# CONN.net
KiCad netlist of a schematic drawn in Altium Designer
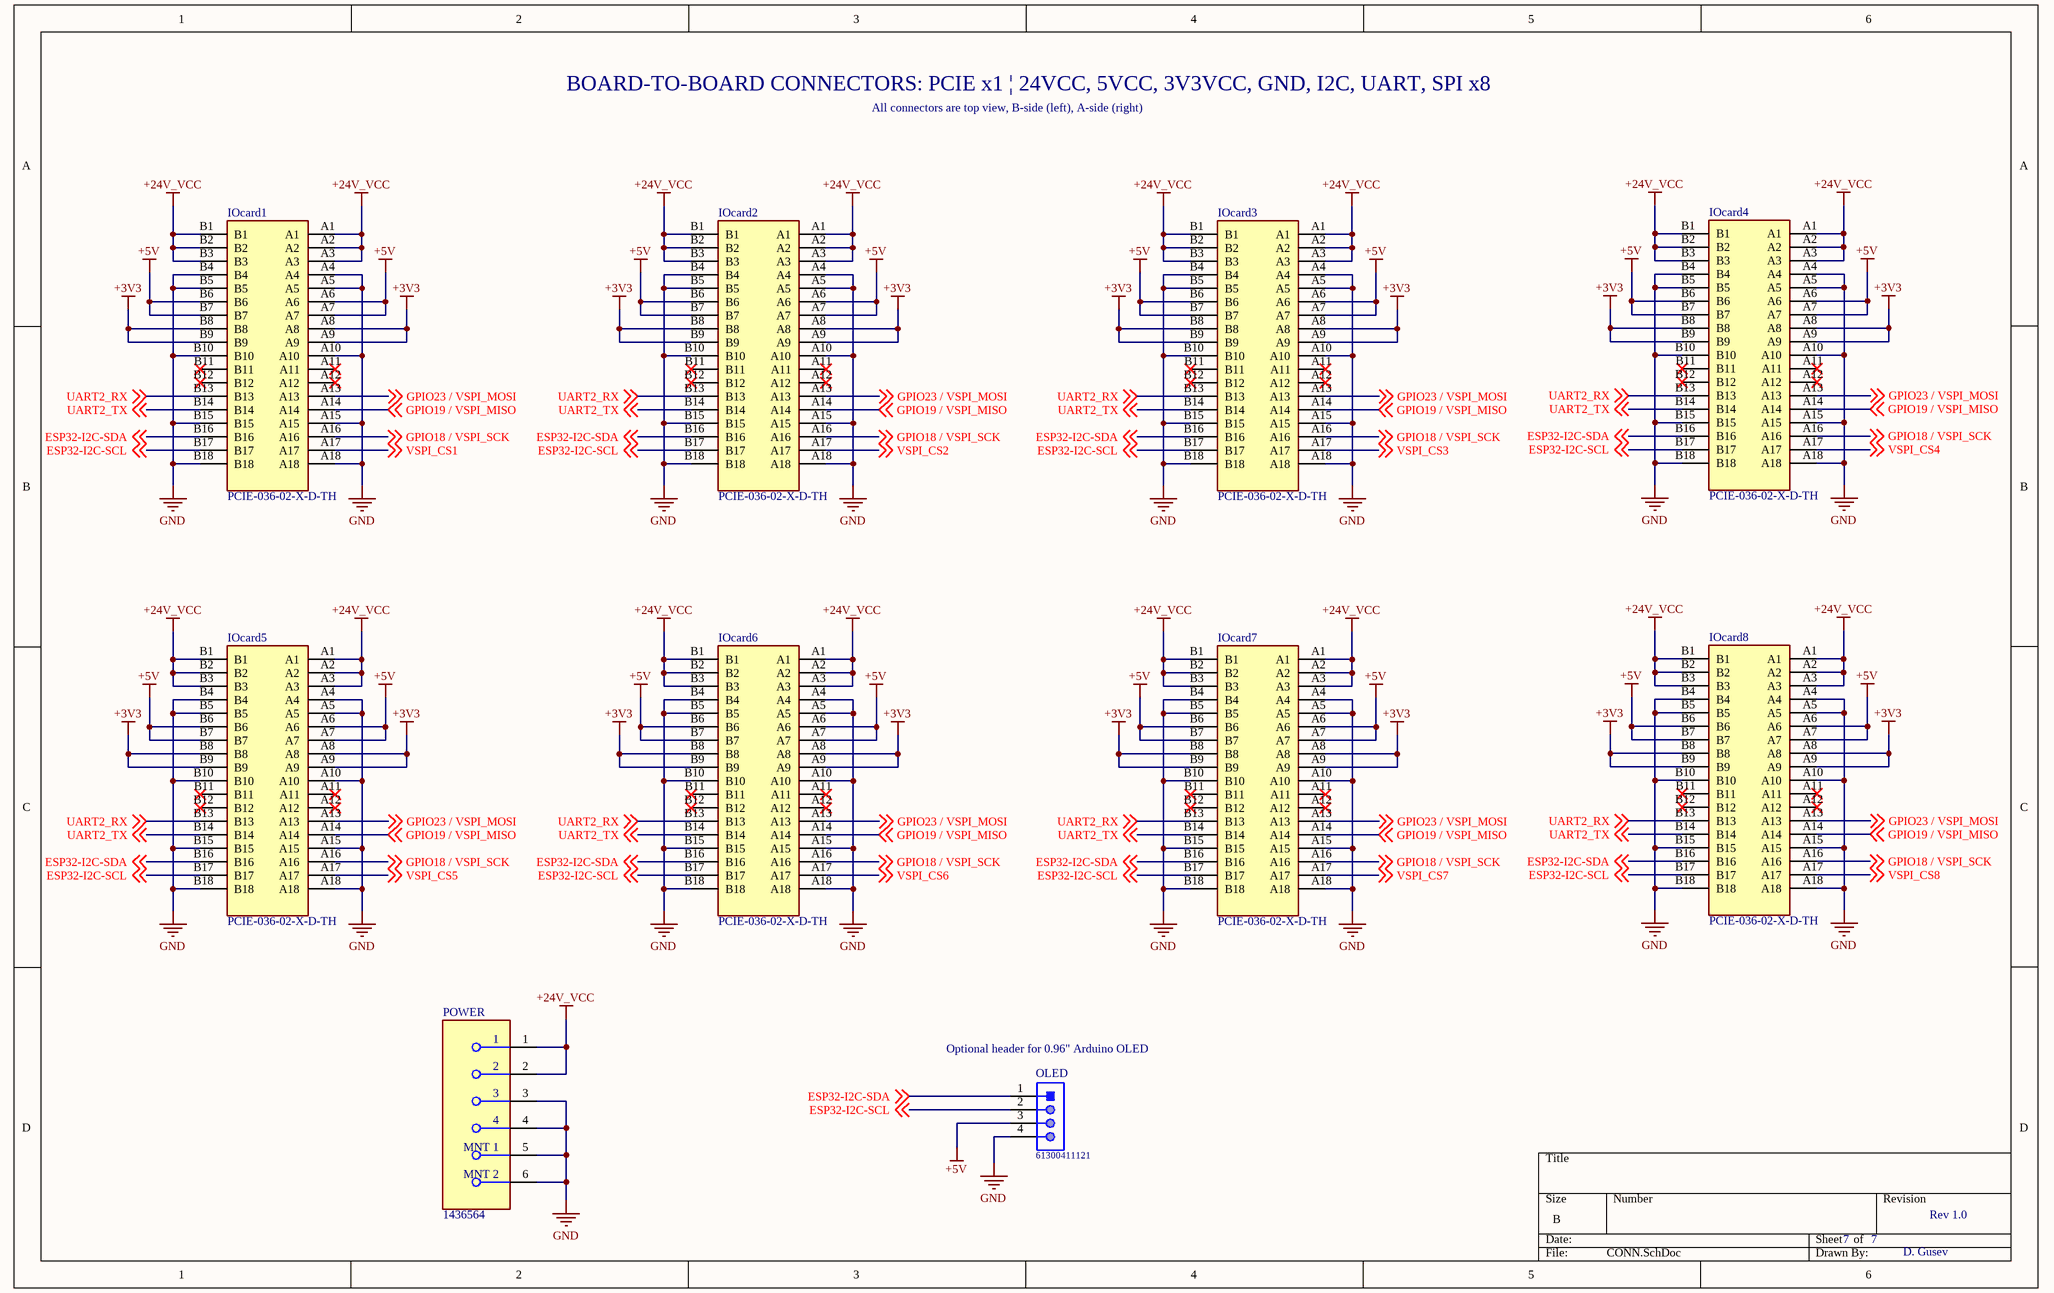
[diagram p0: CONN.SchDoc]

(export (version "E")
  (design (tool "Eeschema 10.0.6"))
  (components
    (comp (ref "IOcard1")
      (value "PCIE-036-02-X-D-TH")
      (footprint "SAMTEC_PCIE-036-02-X-D-TH")
      (description "1.00 mm PCI ExpressÂ® Edge Card Connector")
      (fields (field (name "MF") "Samtec"))
      (libsource (lib "ESP32_INDUSTRIAL_IO_BASEBOARD") (part "PCIE-036-02-X-D-TH"))
    )
    (comp (ref "IOcard2")
      (value "PCIE-036-02-X-D-TH")
      (footprint "SAMTEC_PCIE-036-02-X-D-TH")
      (description "1.00 mm PCI ExpressÂ® Edge Card Connector")
      (fields (field (name "MF") "Samtec"))
      (libsource (lib "ESP32_INDUSTRIAL_IO_BASEBOARD") (part "PCIE-036-02-X-D-TH"))
    )
    (comp (ref "IOcard3")
      (value "PCIE-036-02-X-D-TH")
      (footprint "SAMTEC_PCIE-036-02-X-D-TH")
      (description "1.00 mm PCI ExpressÂ® Edge Card Connector")
      (fields (field (name "MF") "Samtec"))
      (libsource (lib "ESP32_INDUSTRIAL_IO_BASEBOARD") (part "PCIE-036-02-X-D-TH"))
    )
    (comp (ref "IOcard4")
      (value "PCIE-036-02-X-D-TH")
      (footprint "SAMTEC_PCIE-036-02-X-D-TH")
      (description "1.00 mm PCI ExpressÂ® Edge Card Connector")
      (fields (field (name "MF") "Samtec"))
      (libsource (lib "ESP32_INDUSTRIAL_IO_BASEBOARD") (part "PCIE-036-02-X-D-TH"))
    )
    (comp (ref "IOcard5")
      (value "PCIE-036-02-X-D-TH")
      (footprint "SAMTEC_PCIE-036-02-X-D-TH")
      (description "1.00 mm PCI ExpressÂ® Edge Card Connector")
      (fields (field (name "MF") "Samtec"))
      (libsource (lib "ESP32_INDUSTRIAL_IO_BASEBOARD") (part "PCIE-036-02-X-D-TH"))
    )
    (comp (ref "IOcard6")
      (value "PCIE-036-02-X-D-TH")
      (footprint "SAMTEC_PCIE-036-02-X-D-TH")
      (description "1.00 mm PCI ExpressÂ® Edge Card Connector")
      (fields (field (name "MF") "Samtec"))
      (libsource (lib "ESP32_INDUSTRIAL_IO_BASEBOARD") (part "PCIE-036-02-X-D-TH"))
    )
    (comp (ref "IOcard7")
      (value "PCIE-036-02-X-D-TH")
      (footprint "SAMTEC_PCIE-036-02-X-D-TH")
      (description "1.00 mm PCI ExpressÂ® Edge Card Connector")
      (fields (field (name "MF") "Samtec"))
      (libsource (lib "ESP32_INDUSTRIAL_IO_BASEBOARD") (part "PCIE-036-02-X-D-TH"))
    )
    (comp (ref "IOcard8")
      (value "PCIE-036-02-X-D-TH")
      (footprint "SAMTEC_PCIE-036-02-X-D-TH")
      (description "1.00 mm PCI ExpressÂ® Edge Card Connector")
      (fields (field (name "MF") "Samtec"))
      (libsource (lib "ESP32_INDUSTRIAL_IO_BASEBOARD") (part "PCIE-036-02-X-D-TH"))
    )
    (comp (ref "OLED")
      (value "61300411121")
      (footprint "61300411121")
      (description "THT Vertical Pin Header WR-PHD, Pitch 2.54 mm, Single Row, 4 pins")
      (fields (field (name "MANUFACTURER") "Wurth Elektronik") (field (name "PUBLISHER") "WurthElektronik"))
      (libsource (lib "Altium Content Vault") (part "WE-CN-1P-M-R4"))
    )
    (comp (ref "POWER")
      (value "1436564")
      (footprint "FP-1436564-MFG")
      (description "Circular Metric Connectors FEMALE 4P A-CODED")
      (fields (field (name "OCTOPART") "https://octopart.com/1436564-phoenix+contact-12805506"))
      (libsource (lib "Altium Content Vault") (part "3cf8230c7ca2247c71501eddf00a6f6"))
    )
  )
  (nets
    (net (code "1") (name "+3V3") (class "Default")
      (node (ref "IOcard1") (pin "A8") (pinfunction "A8_A8") (pintype "passive"))
      (node (ref "IOcard1") (pin "A9") (pinfunction "A9_A9") (pintype "passive"))
      (node (ref "IOcard1") (pin "B8") (pinfunction "B8_B8") (pintype "passive"))
      (node (ref "IOcard1") (pin "B9") (pinfunction "B9_B9") (pintype "passive"))
      (node (ref "IOcard2") (pin "A8") (pinfunction "A8_A8") (pintype "passive"))
      (node (ref "IOcard2") (pin "A9") (pinfunction "A9_A9") (pintype "passive"))
      (node (ref "IOcard2") (pin "B8") (pinfunction "B8_B8") (pintype "passive"))
      (node (ref "IOcard2") (pin "B9") (pinfunction "B9_B9") (pintype "passive"))
      (node (ref "IOcard3") (pin "A8") (pinfunction "A8_A8") (pintype "passive"))
      (node (ref "IOcard3") (pin "A9") (pinfunction "A9_A9") (pintype "passive"))
      (node (ref "IOcard3") (pin "B8") (pinfunction "B8_B8") (pintype "passive"))
      (node (ref "IOcard3") (pin "B9") (pinfunction "B9_B9") (pintype "passive"))
      (node (ref "IOcard4") (pin "A8") (pinfunction "A8_A8") (pintype "passive"))
      (node (ref "IOcard4") (pin "A9") (pinfunction "A9_A9") (pintype "passive"))
      (node (ref "IOcard4") (pin "B8") (pinfunction "B8_B8") (pintype "passive"))
      (node (ref "IOcard4") (pin "B9") (pinfunction "B9_B9") (pintype "passive"))
      (node (ref "IOcard5") (pin "A8") (pinfunction "A8_A8") (pintype "passive"))
      (node (ref "IOcard5") (pin "A9") (pinfunction "A9_A9") (pintype "passive"))
      (node (ref "IOcard5") (pin "B8") (pinfunction "B8_B8") (pintype "passive"))
      (node (ref "IOcard5") (pin "B9") (pinfunction "B9_B9") (pintype "passive"))
      (node (ref "IOcard6") (pin "A8") (pinfunction "A8_A8") (pintype "passive"))
      (node (ref "IOcard6") (pin "A9") (pinfunction "A9_A9") (pintype "passive"))
      (node (ref "IOcard6") (pin "B8") (pinfunction "B8_B8") (pintype "passive"))
      (node (ref "IOcard6") (pin "B9") (pinfunction "B9_B9") (pintype "passive"))
      (node (ref "IOcard7") (pin "A8") (pinfunction "A8_A8") (pintype "passive"))
      (node (ref "IOcard7") (pin "A9") (pinfunction "A9_A9") (pintype "passive"))
      (node (ref "IOcard7") (pin "B8") (pinfunction "B8_B8") (pintype "passive"))
      (node (ref "IOcard7") (pin "B9") (pinfunction "B9_B9") (pintype "passive"))
      (node (ref "IOcard8") (pin "A8") (pinfunction "A8_A8") (pintype "passive"))
      (node (ref "IOcard8") (pin "A9") (pinfunction "A9_A9") (pintype "passive"))
      (node (ref "IOcard8") (pin "B8") (pinfunction "B8_B8") (pintype "passive"))
      (node (ref "IOcard8") (pin "B9") (pinfunction "B9_B9") (pintype "passive"))
    )
    (net (code "2") (name "+5V") (class "Default")
      (node (ref "IOcard1") (pin "A6") (pinfunction "A6_A6") (pintype "passive"))
      (node (ref "IOcard1") (pin "A7") (pinfunction "A7_A7") (pintype "passive"))
      (node (ref "IOcard1") (pin "B6") (pinfunction "B6_B6") (pintype "passive"))
      (node (ref "IOcard1") (pin "B7") (pinfunction "B7_B7") (pintype "passive"))
      (node (ref "IOcard2") (pin "A6") (pinfunction "A6_A6") (pintype "passive"))
      (node (ref "IOcard2") (pin "A7") (pinfunction "A7_A7") (pintype "passive"))
      (node (ref "IOcard2") (pin "B6") (pinfunction "B6_B6") (pintype "passive"))
      (node (ref "IOcard2") (pin "B7") (pinfunction "B7_B7") (pintype "passive"))
      (node (ref "IOcard3") (pin "A6") (pinfunction "A6_A6") (pintype "passive"))
      (node (ref "IOcard3") (pin "A7") (pinfunction "A7_A7") (pintype "passive"))
      (node (ref "IOcard3") (pin "B6") (pinfunction "B6_B6") (pintype "passive"))
      (node (ref "IOcard3") (pin "B7") (pinfunction "B7_B7") (pintype "passive"))
      (node (ref "IOcard4") (pin "A6") (pinfunction "A6_A6") (pintype "passive"))
      (node (ref "IOcard4") (pin "A7") (pinfunction "A7_A7") (pintype "passive"))
      (node (ref "IOcard4") (pin "B6") (pinfunction "B6_B6") (pintype "passive"))
      (node (ref "IOcard4") (pin "B7") (pinfunction "B7_B7") (pintype "passive"))
      (node (ref "IOcard5") (pin "A6") (pinfunction "A6_A6") (pintype "passive"))
      (node (ref "IOcard5") (pin "A7") (pinfunction "A7_A7") (pintype "passive"))
      (node (ref "IOcard5") (pin "B6") (pinfunction "B6_B6") (pintype "passive"))
      (node (ref "IOcard5") (pin "B7") (pinfunction "B7_B7") (pintype "passive"))
      (node (ref "IOcard6") (pin "A6") (pinfunction "A6_A6") (pintype "passive"))
      (node (ref "IOcard6") (pin "A7") (pinfunction "A7_A7") (pintype "passive"))
      (node (ref "IOcard6") (pin "B6") (pinfunction "B6_B6") (pintype "passive"))
      (node (ref "IOcard6") (pin "B7") (pinfunction "B7_B7") (pintype "passive"))
      (node (ref "IOcard7") (pin "A6") (pinfunction "A6_A6") (pintype "passive"))
      (node (ref "IOcard7") (pin "A7") (pinfunction "A7_A7") (pintype "passive"))
      (node (ref "IOcard7") (pin "B6") (pinfunction "B6_B6") (pintype "passive"))
      (node (ref "IOcard7") (pin "B7") (pinfunction "B7_B7") (pintype "passive"))
      (node (ref "IOcard8") (pin "A6") (pinfunction "A6_A6") (pintype "passive"))
      (node (ref "IOcard8") (pin "A7") (pinfunction "A7_A7") (pintype "passive"))
      (node (ref "IOcard8") (pin "B6") (pinfunction "B6_B6") (pintype "passive"))
      (node (ref "IOcard8") (pin "B7") (pinfunction "B7_B7") (pintype "passive"))
      (node (ref "OLED") (pin "3") (pinfunction "3_3") (pintype "passive"))
    )
    (net (code "3") (name "+24V_VCC") (class "Default")
      (node (ref "IOcard1") (pin "A1") (pinfunction "A1_A1") (pintype "passive"))
      (node (ref "IOcard1") (pin "A2") (pinfunction "A2_A2") (pintype "passive"))
      (node (ref "IOcard1") (pin "A3") (pinfunction "A3_A3") (pintype "passive"))
      (node (ref "IOcard1") (pin "B1") (pinfunction "B1_B1") (pintype "passive"))
      (node (ref "IOcard1") (pin "B2") (pinfunction "B2_B2") (pintype "passive"))
      (node (ref "IOcard1") (pin "B3") (pinfunction "B3_B3") (pintype "passive"))
      (node (ref "IOcard2") (pin "A1") (pinfunction "A1_A1") (pintype "passive"))
      (node (ref "IOcard2") (pin "A2") (pinfunction "A2_A2") (pintype "passive"))
      (node (ref "IOcard2") (pin "A3") (pinfunction "A3_A3") (pintype "passive"))
      (node (ref "IOcard2") (pin "B1") (pinfunction "B1_B1") (pintype "passive"))
      (node (ref "IOcard2") (pin "B2") (pinfunction "B2_B2") (pintype "passive"))
      (node (ref "IOcard2") (pin "B3") (pinfunction "B3_B3") (pintype "passive"))
      (node (ref "IOcard3") (pin "A1") (pinfunction "A1_A1") (pintype "passive"))
      (node (ref "IOcard3") (pin "A2") (pinfunction "A2_A2") (pintype "passive"))
      (node (ref "IOcard3") (pin "A3") (pinfunction "A3_A3") (pintype "passive"))
      (node (ref "IOcard3") (pin "B1") (pinfunction "B1_B1") (pintype "passive"))
      (node (ref "IOcard3") (pin "B2") (pinfunction "B2_B2") (pintype "passive"))
      (node (ref "IOcard3") (pin "B3") (pinfunction "B3_B3") (pintype "passive"))
      (node (ref "IOcard4") (pin "A1") (pinfunction "A1_A1") (pintype "passive"))
      (node (ref "IOcard4") (pin "A2") (pinfunction "A2_A2") (pintype "passive"))
      (node (ref "IOcard4") (pin "A3") (pinfunction "A3_A3") (pintype "passive"))
      (node (ref "IOcard4") (pin "B1") (pinfunction "B1_B1") (pintype "passive"))
      (node (ref "IOcard4") (pin "B2") (pinfunction "B2_B2") (pintype "passive"))
      (node (ref "IOcard4") (pin "B3") (pinfunction "B3_B3") (pintype "passive"))
      (node (ref "IOcard5") (pin "A1") (pinfunction "A1_A1") (pintype "passive"))
      (node (ref "IOcard5") (pin "A2") (pinfunction "A2_A2") (pintype "passive"))
      (node (ref "IOcard5") (pin "A3") (pinfunction "A3_A3") (pintype "passive"))
      (node (ref "IOcard5") (pin "B1") (pinfunction "B1_B1") (pintype "passive"))
      (node (ref "IOcard5") (pin "B2") (pinfunction "B2_B2") (pintype "passive"))
      (node (ref "IOcard5") (pin "B3") (pinfunction "B3_B3") (pintype "passive"))
      (node (ref "IOcard6") (pin "A1") (pinfunction "A1_A1") (pintype "passive"))
      (node (ref "IOcard6") (pin "A2") (pinfunction "A2_A2") (pintype "passive"))
      (node (ref "IOcard6") (pin "A3") (pinfunction "A3_A3") (pintype "passive"))
      (node (ref "IOcard6") (pin "B1") (pinfunction "B1_B1") (pintype "passive"))
      (node (ref "IOcard6") (pin "B2") (pinfunction "B2_B2") (pintype "passive"))
      (node (ref "IOcard6") (pin "B3") (pinfunction "B3_B3") (pintype "passive"))
      (node (ref "IOcard7") (pin "A1") (pinfunction "A1_A1") (pintype "passive"))
      (node (ref "IOcard7") (pin "A2") (pinfunction "A2_A2") (pintype "passive"))
      (node (ref "IOcard7") (pin "A3") (pinfunction "A3_A3") (pintype "passive"))
      (node (ref "IOcard7") (pin "B1") (pinfunction "B1_B1") (pintype "passive"))
      (node (ref "IOcard7") (pin "B2") (pinfunction "B2_B2") (pintype "passive"))
      (node (ref "IOcard7") (pin "B3") (pinfunction "B3_B3") (pintype "passive"))
      (node (ref "IOcard8") (pin "A1") (pinfunction "A1_A1") (pintype "passive"))
      (node (ref "IOcard8") (pin "A2") (pinfunction "A2_A2") (pintype "passive"))
      (node (ref "IOcard8") (pin "A3") (pinfunction "A3_A3") (pintype "passive"))
      (node (ref "IOcard8") (pin "B1") (pinfunction "B1_B1") (pintype "passive"))
      (node (ref "IOcard8") (pin "B2") (pinfunction "B2_B2") (pintype "passive"))
      (node (ref "IOcard8") (pin "B3") (pinfunction "B3_B3") (pintype "passive"))
      (node (ref "POWER") (pin "1") (pinfunction "1_1") (pintype "passive"))
      (node (ref "POWER") (pin "2") (pinfunction "2_2") (pintype "passive"))
    )
    (net (code "4") (name "ESP32-I2C-SCL") (class "Default")
      (node (ref "IOcard1") (pin "B17") (pinfunction "B17_B17") (pintype "passive"))
      (node (ref "IOcard2") (pin "B17") (pinfunction "B17_B17") (pintype "passive"))
      (node (ref "IOcard3") (pin "B17") (pinfunction "B17_B17") (pintype "passive"))
      (node (ref "IOcard4") (pin "B17") (pinfunction "B17_B17") (pintype "passive"))
      (node (ref "IOcard5") (pin "B17") (pinfunction "B17_B17") (pintype "passive"))
      (node (ref "IOcard6") (pin "B17") (pinfunction "B17_B17") (pintype "passive"))
      (node (ref "IOcard7") (pin "B17") (pinfunction "B17_B17") (pintype "passive"))
      (node (ref "IOcard8") (pin "B17") (pinfunction "B17_B17") (pintype "passive"))
      (node (ref "OLED") (pin "2") (pinfunction "2_2") (pintype "passive"))
    )
    (net (code "5") (name "ESP32-I2C-SDA") (class "Default")
      (node (ref "IOcard1") (pin "B16") (pinfunction "B16_B16") (pintype "passive"))
      (node (ref "IOcard2") (pin "B16") (pinfunction "B16_B16") (pintype "passive"))
      (node (ref "IOcard3") (pin "B16") (pinfunction "B16_B16") (pintype "passive"))
      (node (ref "IOcard4") (pin "B16") (pinfunction "B16_B16") (pintype "passive"))
      (node (ref "IOcard5") (pin "B16") (pinfunction "B16_B16") (pintype "passive"))
      (node (ref "IOcard6") (pin "B16") (pinfunction "B16_B16") (pintype "passive"))
      (node (ref "IOcard7") (pin "B16") (pinfunction "B16_B16") (pintype "passive"))
      (node (ref "IOcard8") (pin "B16") (pinfunction "B16_B16") (pintype "passive"))
      (node (ref "OLED") (pin "1") (pinfunction "1_1") (pintype "passive"))
    )
    (net (code "6") (name "GND") (class "Default")
      (node (ref "IOcard1") (pin "A10") (pinfunction "A10_A10") (pintype "passive"))
      (node (ref "IOcard1") (pin "A15") (pinfunction "A15_A15") (pintype "passive"))
      (node (ref "IOcard1") (pin "A18") (pinfunction "A18_A18") (pintype "passive"))
      (node (ref "IOcard1") (pin "A4") (pinfunction "A4_A4") (pintype "passive"))
      (node (ref "IOcard1") (pin "A5") (pinfunction "A5_A5") (pintype "passive"))
      (node (ref "IOcard1") (pin "B10") (pinfunction "B10_B10") (pintype "passive"))
      (node (ref "IOcard1") (pin "B15") (pinfunction "B15_B15") (pintype "passive"))
      (node (ref "IOcard1") (pin "B18") (pinfunction "B18_B18") (pintype "passive"))
      (node (ref "IOcard1") (pin "B4") (pinfunction "B4_B4") (pintype "passive"))
      (node (ref "IOcard1") (pin "B5") (pinfunction "B5_B5") (pintype "passive"))
      (node (ref "IOcard2") (pin "A10") (pinfunction "A10_A10") (pintype "passive"))
      (node (ref "IOcard2") (pin "A15") (pinfunction "A15_A15") (pintype "passive"))
      (node (ref "IOcard2") (pin "A18") (pinfunction "A18_A18") (pintype "passive"))
      (node (ref "IOcard2") (pin "A4") (pinfunction "A4_A4") (pintype "passive"))
      (node (ref "IOcard2") (pin "A5") (pinfunction "A5_A5") (pintype "passive"))
      (node (ref "IOcard2") (pin "B10") (pinfunction "B10_B10") (pintype "passive"))
      (node (ref "IOcard2") (pin "B15") (pinfunction "B15_B15") (pintype "passive"))
      (node (ref "IOcard2") (pin "B18") (pinfunction "B18_B18") (pintype "passive"))
      (node (ref "IOcard2") (pin "B4") (pinfunction "B4_B4") (pintype "passive"))
      (node (ref "IOcard2") (pin "B5") (pinfunction "B5_B5") (pintype "passive"))
      (node (ref "IOcard3") (pin "A10") (pinfunction "A10_A10") (pintype "passive"))
      (node (ref "IOcard3") (pin "A15") (pinfunction "A15_A15") (pintype "passive"))
      (node (ref "IOcard3") (pin "A18") (pinfunction "A18_A18") (pintype "passive"))
      (node (ref "IOcard3") (pin "A4") (pinfunction "A4_A4") (pintype "passive"))
      (node (ref "IOcard3") (pin "A5") (pinfunction "A5_A5") (pintype "passive"))
      (node (ref "IOcard3") (pin "B10") (pinfunction "B10_B10") (pintype "passive"))
      (node (ref "IOcard3") (pin "B15") (pinfunction "B15_B15") (pintype "passive"))
      (node (ref "IOcard3") (pin "B18") (pinfunction "B18_B18") (pintype "passive"))
      (node (ref "IOcard3") (pin "B4") (pinfunction "B4_B4") (pintype "passive"))
      (node (ref "IOcard3") (pin "B5") (pinfunction "B5_B5") (pintype "passive"))
      (node (ref "IOcard4") (pin "A10") (pinfunction "A10_A10") (pintype "passive"))
      (node (ref "IOcard4") (pin "A15") (pinfunction "A15_A15") (pintype "passive"))
      (node (ref "IOcard4") (pin "A18") (pinfunction "A18_A18") (pintype "passive"))
      (node (ref "IOcard4") (pin "A4") (pinfunction "A4_A4") (pintype "passive"))
      (node (ref "IOcard4") (pin "A5") (pinfunction "A5_A5") (pintype "passive"))
      (node (ref "IOcard4") (pin "B10") (pinfunction "B10_B10") (pintype "passive"))
      (node (ref "IOcard4") (pin "B15") (pinfunction "B15_B15") (pintype "passive"))
      (node (ref "IOcard4") (pin "B18") (pinfunction "B18_B18") (pintype "passive"))
      (node (ref "IOcard4") (pin "B4") (pinfunction "B4_B4") (pintype "passive"))
      (node (ref "IOcard4") (pin "B5") (pinfunction "B5_B5") (pintype "passive"))
      (node (ref "IOcard5") (pin "A10") (pinfunction "A10_A10") (pintype "passive"))
      (node (ref "IOcard5") (pin "A15") (pinfunction "A15_A15") (pintype "passive"))
      (node (ref "IOcard5") (pin "A18") (pinfunction "A18_A18") (pintype "passive"))
      (node (ref "IOcard5") (pin "A4") (pinfunction "A4_A4") (pintype "passive"))
      (node (ref "IOcard5") (pin "A5") (pinfunction "A5_A5") (pintype "passive"))
      (node (ref "IOcard5") (pin "B10") (pinfunction "B10_B10") (pintype "passive"))
      (node (ref "IOcard5") (pin "B15") (pinfunction "B15_B15") (pintype "passive"))
      (node (ref "IOcard5") (pin "B18") (pinfunction "B18_B18") (pintype "passive"))
      (node (ref "IOcard5") (pin "B4") (pinfunction "B4_B4") (pintype "passive"))
      (node (ref "IOcard5") (pin "B5") (pinfunction "B5_B5") (pintype "passive"))
      (node (ref "IOcard6") (pin "A10") (pinfunction "A10_A10") (pintype "passive"))
      (node (ref "IOcard6") (pin "A15") (pinfunction "A15_A15") (pintype "passive"))
      (node (ref "IOcard6") (pin "A18") (pinfunction "A18_A18") (pintype "passive"))
      (node (ref "IOcard6") (pin "A4") (pinfunction "A4_A4") (pintype "passive"))
      (node (ref "IOcard6") (pin "A5") (pinfunction "A5_A5") (pintype "passive"))
      (node (ref "IOcard6") (pin "B10") (pinfunction "B10_B10") (pintype "passive"))
      (node (ref "IOcard6") (pin "B15") (pinfunction "B15_B15") (pintype "passive"))
      (node (ref "IOcard6") (pin "B18") (pinfunction "B18_B18") (pintype "passive"))
      (node (ref "IOcard6") (pin "B4") (pinfunction "B4_B4") (pintype "passive"))
      (node (ref "IOcard6") (pin "B5") (pinfunction "B5_B5") (pintype "passive"))
      (node (ref "IOcard7") (pin "A10") (pinfunction "A10_A10") (pintype "passive"))
      (node (ref "IOcard7") (pin "A15") (pinfunction "A15_A15") (pintype "passive"))
      (node (ref "IOcard7") (pin "A18") (pinfunction "A18_A18") (pintype "passive"))
      (node (ref "IOcard7") (pin "A4") (pinfunction "A4_A4") (pintype "passive"))
      (node (ref "IOcard7") (pin "A5") (pinfunction "A5_A5") (pintype "passive"))
      (node (ref "IOcard7") (pin "B10") (pinfunction "B10_B10") (pintype "passive"))
      (node (ref "IOcard7") (pin "B15") (pinfunction "B15_B15") (pintype "passive"))
      (node (ref "IOcard7") (pin "B18") (pinfunction "B18_B18") (pintype "passive"))
      (node (ref "IOcard7") (pin "B4") (pinfunction "B4_B4") (pintype "passive"))
      (node (ref "IOcard7") (pin "B5") (pinfunction "B5_B5") (pintype "passive"))
      (node (ref "IOcard8") (pin "A10") (pinfunction "A10_A10") (pintype "passive"))
      (node (ref "IOcard8") (pin "A15") (pinfunction "A15_A15") (pintype "passive"))
      (node (ref "IOcard8") (pin "A18") (pinfunction "A18_A18") (pintype "passive"))
      (node (ref "IOcard8") (pin "A4") (pinfunction "A4_A4") (pintype "passive"))
      (node (ref "IOcard8") (pin "A5") (pinfunction "A5_A5") (pintype "passive"))
      (node (ref "IOcard8") (pin "B10") (pinfunction "B10_B10") (pintype "passive"))
      (node (ref "IOcard8") (pin "B15") (pinfunction "B15_B15") (pintype "passive"))
      (node (ref "IOcard8") (pin "B18") (pinfunction "B18_B18") (pintype "passive"))
      (node (ref "IOcard8") (pin "B4") (pinfunction "B4_B4") (pintype "passive"))
      (node (ref "IOcard8") (pin "B5") (pinfunction "B5_B5") (pintype "passive"))
      (node (ref "OLED") (pin "4") (pinfunction "4_4") (pintype "passive"))
      (node (ref "POWER") (pin "3") (pinfunction "3_3") (pintype "passive"))
      (node (ref "POWER") (pin "4") (pinfunction "4_4") (pintype "passive"))
      (node (ref "POWER") (pin "5") (pinfunction "MNT_1_5") (pintype "passive"))
      (node (ref "POWER") (pin "6") (pinfunction "MNT_2_6") (pintype "passive"))
    )
    (net (code "7") (name "GPIO18 {slash} VSPI_SCK") (class "Default")
      (node (ref "IOcard1") (pin "A16") (pinfunction "A16_A16") (pintype "passive"))
      (node (ref "IOcard2") (pin "A16") (pinfunction "A16_A16") (pintype "passive"))
      (node (ref "IOcard3") (pin "A16") (pinfunction "A16_A16") (pintype "passive"))
      (node (ref "IOcard4") (pin "A16") (pinfunction "A16_A16") (pintype "passive"))
      (node (ref "IOcard5") (pin "A16") (pinfunction "A16_A16") (pintype "passive"))
      (node (ref "IOcard6") (pin "A16") (pinfunction "A16_A16") (pintype "passive"))
      (node (ref "IOcard7") (pin "A16") (pinfunction "A16_A16") (pintype "passive"))
      (node (ref "IOcard8") (pin "A16") (pinfunction "A16_A16") (pintype "passive"))
    )
    (net (code "8") (name "GPIO19 {slash} VSPI_MISO") (class "Default")
      (node (ref "IOcard1") (pin "A14") (pinfunction "A14_A14") (pintype "passive"))
      (node (ref "IOcard2") (pin "A14") (pinfunction "A14_A14") (pintype "passive"))
      (node (ref "IOcard3") (pin "A14") (pinfunction "A14_A14") (pintype "passive"))
      (node (ref "IOcard4") (pin "A14") (pinfunction "A14_A14") (pintype "passive"))
      (node (ref "IOcard5") (pin "A14") (pinfunction "A14_A14") (pintype "passive"))
      (node (ref "IOcard6") (pin "A14") (pinfunction "A14_A14") (pintype "passive"))
      (node (ref "IOcard7") (pin "A14") (pinfunction "A14_A14") (pintype "passive"))
      (node (ref "IOcard8") (pin "A14") (pinfunction "A14_A14") (pintype "passive"))
    )
    (net (code "9") (name "GPIO23 {slash} VSPI_MOSI") (class "Default")
      (node (ref "IOcard1") (pin "A13") (pinfunction "A13_A13") (pintype "passive"))
      (node (ref "IOcard2") (pin "A13") (pinfunction "A13_A13") (pintype "passive"))
      (node (ref "IOcard3") (pin "A13") (pinfunction "A13_A13") (pintype "passive"))
      (node (ref "IOcard4") (pin "A13") (pinfunction "A13_A13") (pintype "passive"))
      (node (ref "IOcard5") (pin "A13") (pinfunction "A13_A13") (pintype "passive"))
      (node (ref "IOcard6") (pin "A13") (pinfunction "A13_A13") (pintype "passive"))
      (node (ref "IOcard7") (pin "A13") (pinfunction "A13_A13") (pintype "passive"))
      (node (ref "IOcard8") (pin "A13") (pinfunction "A13_A13") (pintype "passive"))
    )
    (net (code "10") (name "UART2_RX") (class "Default")
      (node (ref "IOcard1") (pin "B13") (pinfunction "B13_B13") (pintype "passive"))
      (node (ref "IOcard2") (pin "B13") (pinfunction "B13_B13") (pintype "passive"))
      (node (ref "IOcard3") (pin "B13") (pinfunction "B13_B13") (pintype "passive"))
      (node (ref "IOcard4") (pin "B13") (pinfunction "B13_B13") (pintype "passive"))
      (node (ref "IOcard5") (pin "B13") (pinfunction "B13_B13") (pintype "passive"))
      (node (ref "IOcard6") (pin "B13") (pinfunction "B13_B13") (pintype "passive"))
      (node (ref "IOcard7") (pin "B13") (pinfunction "B13_B13") (pintype "passive"))
      (node (ref "IOcard8") (pin "B13") (pinfunction "B13_B13") (pintype "passive"))
    )
    (net (code "11") (name "UART2_TX") (class "Default")
      (node (ref "IOcard1") (pin "B14") (pinfunction "B14_B14") (pintype "passive"))
      (node (ref "IOcard2") (pin "B14") (pinfunction "B14_B14") (pintype "passive"))
      (node (ref "IOcard3") (pin "B14") (pinfunction "B14_B14") (pintype "passive"))
      (node (ref "IOcard4") (pin "B14") (pinfunction "B14_B14") (pintype "passive"))
      (node (ref "IOcard5") (pin "B14") (pinfunction "B14_B14") (pintype "passive"))
      (node (ref "IOcard6") (pin "B14") (pinfunction "B14_B14") (pintype "passive"))
      (node (ref "IOcard7") (pin "B14") (pinfunction "B14_B14") (pintype "passive"))
      (node (ref "IOcard8") (pin "B14") (pinfunction "B14_B14") (pintype "passive"))
    )
    (net (code "12") (name "VSPI_CS1") (class "Default")
      (node (ref "IOcard1") (pin "A17") (pinfunction "A17_A17") (pintype "passive"))
    )
    (net (code "13") (name "VSPI_CS2") (class "Default")
      (node (ref "IOcard2") (pin "A17") (pinfunction "A17_A17") (pintype "passive"))
    )
    (net (code "14") (name "VSPI_CS3") (class "Default")
      (node (ref "IOcard3") (pin "A17") (pinfunction "A17_A17") (pintype "passive"))
    )
    (net (code "15") (name "VSPI_CS4") (class "Default")
      (node (ref "IOcard4") (pin "A17") (pinfunction "A17_A17") (pintype "passive"))
    )
    (net (code "16") (name "VSPI_CS5") (class "Default")
      (node (ref "IOcard5") (pin "A17") (pinfunction "A17_A17") (pintype "passive"))
    )
    (net (code "17") (name "VSPI_CS6") (class "Default")
      (node (ref "IOcard6") (pin "A17") (pinfunction "A17_A17") (pintype "passive"))
    )
    (net (code "18") (name "VSPI_CS7") (class "Default")
      (node (ref "IOcard7") (pin "A17") (pinfunction "A17_A17") (pintype "passive"))
    )
    (net (code "19") (name "VSPI_CS8") (class "Default")
      (node (ref "IOcard8") (pin "A17") (pinfunction "A17_A17") (pintype "passive"))
    )
    (net (code "20") (name "unconnected-(IOcard1-PadA11)") (class "Default")
      (node (ref "IOcard1") (pin "A11") (pinfunction "A11_A11") (pintype "passive+no_connect"))
    )
    (net (code "21") (name "unconnected-(IOcard1-PadA12)") (class "Default")
      (node (ref "IOcard1") (pin "A12") (pinfunction "A12_A12") (pintype "passive+no_connect"))
    )
    (net (code "22") (name "unconnected-(IOcard1-PadB11)") (class "Default")
      (node (ref "IOcard1") (pin "B11") (pinfunction "B11_B11") (pintype "passive+no_connect"))
    )
    (net (code "23") (name "unconnected-(IOcard1-PadB12)") (class "Default")
      (node (ref "IOcard1") (pin "B12") (pinfunction "B12_B12") (pintype "passive+no_connect"))
    )
    (net (code "24") (name "unconnected-(IOcard2-PadA11)") (class "Default")
      (node (ref "IOcard2") (pin "A11") (pinfunction "A11_A11") (pintype "passive+no_connect"))
    )
    (net (code "25") (name "unconnected-(IOcard2-PadA12)") (class "Default")
      (node (ref "IOcard2") (pin "A12") (pinfunction "A12_A12") (pintype "passive+no_connect"))
    )
    (net (code "26") (name "unconnected-(IOcard2-PadB11)") (class "Default")
      (node (ref "IOcard2") (pin "B11") (pinfunction "B11_B11") (pintype "passive+no_connect"))
    )
    (net (code "27") (name "unconnected-(IOcard2-PadB12)") (class "Default")
      (node (ref "IOcard2") (pin "B12") (pinfunction "B12_B12") (pintype "passive+no_connect"))
    )
    (net (code "28") (name "unconnected-(IOcard3-PadA11)") (class "Default")
      (node (ref "IOcard3") (pin "A11") (pinfunction "A11_A11") (pintype "passive+no_connect"))
    )
    (net (code "29") (name "unconnected-(IOcard3-PadA12)") (class "Default")
      (node (ref "IOcard3") (pin "A12") (pinfunction "A12_A12") (pintype "passive+no_connect"))
    )
    (net (code "30") (name "unconnected-(IOcard3-PadB11)") (class "Default")
      (node (ref "IOcard3") (pin "B11") (pinfunction "B11_B11") (pintype "passive+no_connect"))
    )
    (net (code "31") (name "unconnected-(IOcard3-PadB12)") (class "Default")
      (node (ref "IOcard3") (pin "B12") (pinfunction "B12_B12") (pintype "passive+no_connect"))
    )
    (net (code "32") (name "unconnected-(IOcard4-PadA11)") (class "Default")
      (node (ref "IOcard4") (pin "A11") (pinfunction "A11_A11") (pintype "passive+no_connect"))
    )
    (net (code "33") (name "unconnected-(IOcard4-PadA12)") (class "Default")
      (node (ref "IOcard4") (pin "A12") (pinfunction "A12_A12") (pintype "passive+no_connect"))
    )
    (net (code "34") (name "unconnected-(IOcard4-PadB11)") (class "Default")
      (node (ref "IOcard4") (pin "B11") (pinfunction "B11_B11") (pintype "passive+no_connect"))
    )
    (net (code "35") (name "unconnected-(IOcard4-PadB12)") (class "Default")
      (node (ref "IOcard4") (pin "B12") (pinfunction "B12_B12") (pintype "passive+no_connect"))
    )
    (net (code "36") (name "unconnected-(IOcard5-PadA11)") (class "Default")
      (node (ref "IOcard5") (pin "A11") (pinfunction "A11_A11") (pintype "passive+no_connect"))
    )
    (net (code "37") (name "unconnected-(IOcard5-PadA12)") (class "Default")
      (node (ref "IOcard5") (pin "A12") (pinfunction "A12_A12") (pintype "passive+no_connect"))
    )
    (net (code "38") (name "unconnected-(IOcard5-PadB11)") (class "Default")
      (node (ref "IOcard5") (pin "B11") (pinfunction "B11_B11") (pintype "passive+no_connect"))
    )
    (net (code "39") (name "unconnected-(IOcard5-PadB12)") (class "Default")
      (node (ref "IOcard5") (pin "B12") (pinfunction "B12_B12") (pintype "passive+no_connect"))
    )
    (net (code "40") (name "unconnected-(IOcard6-PadA11)") (class "Default")
      (node (ref "IOcard6") (pin "A11") (pinfunction "A11_A11") (pintype "passive+no_connect"))
    )
    (net (code "41") (name "unconnected-(IOcard6-PadA12)") (class "Default")
      (node (ref "IOcard6") (pin "A12") (pinfunction "A12_A12") (pintype "passive+no_connect"))
    )
    (net (code "42") (name "unconnected-(IOcard6-PadB11)") (class "Default")
      (node (ref "IOcard6") (pin "B11") (pinfunction "B11_B11") (pintype "passive+no_connect"))
    )
    (net (code "43") (name "unconnected-(IOcard6-PadB12)") (class "Default")
      (node (ref "IOcard6") (pin "B12") (pinfunction "B12_B12") (pintype "passive+no_connect"))
    )
    (net (code "44") (name "unconnected-(IOcard7-PadA11)") (class "Default")
      (node (ref "IOcard7") (pin "A11") (pinfunction "A11_A11") (pintype "passive+no_connect"))
    )
    (net (code "45") (name "unconnected-(IOcard7-PadA12)") (class "Default")
      (node (ref "IOcard7") (pin "A12") (pinfunction "A12_A12") (pintype "passive+no_connect"))
    )
    (net (code "46") (name "unconnected-(IOcard7-PadB11)") (class "Default")
      (node (ref "IOcard7") (pin "B11") (pinfunction "B11_B11") (pintype "passive+no_connect"))
    )
    (net (code "47") (name "unconnected-(IOcard7-PadB12)") (class "Default")
      (node (ref "IOcard7") (pin "B12") (pinfunction "B12_B12") (pintype "passive+no_connect"))
    )
    (net (code "48") (name "unconnected-(IOcard8-PadA11)") (class "Default")
      (node (ref "IOcard8") (pin "A11") (pinfunction "A11_A11") (pintype "passive+no_connect"))
    )
    (net (code "49") (name "unconnected-(IOcard8-PadA12)") (class "Default")
      (node (ref "IOcard8") (pin "A12") (pinfunction "A12_A12") (pintype "passive+no_connect"))
    )
    (net (code "50") (name "unconnected-(IOcard8-PadB11)") (class "Default")
      (node (ref "IOcard8") (pin "B11") (pinfunction "B11_B11") (pintype "passive+no_connect"))
    )
    (net (code "51") (name "unconnected-(IOcard8-PadB12)") (class "Default")
      (node (ref "IOcard8") (pin "B12") (pinfunction "B12_B12") (pintype "passive+no_connect"))
    )
  )
)
